# LIC_Rack_BB-00_ext.net
KiCad netlist of a schematic drawn in EAGLE
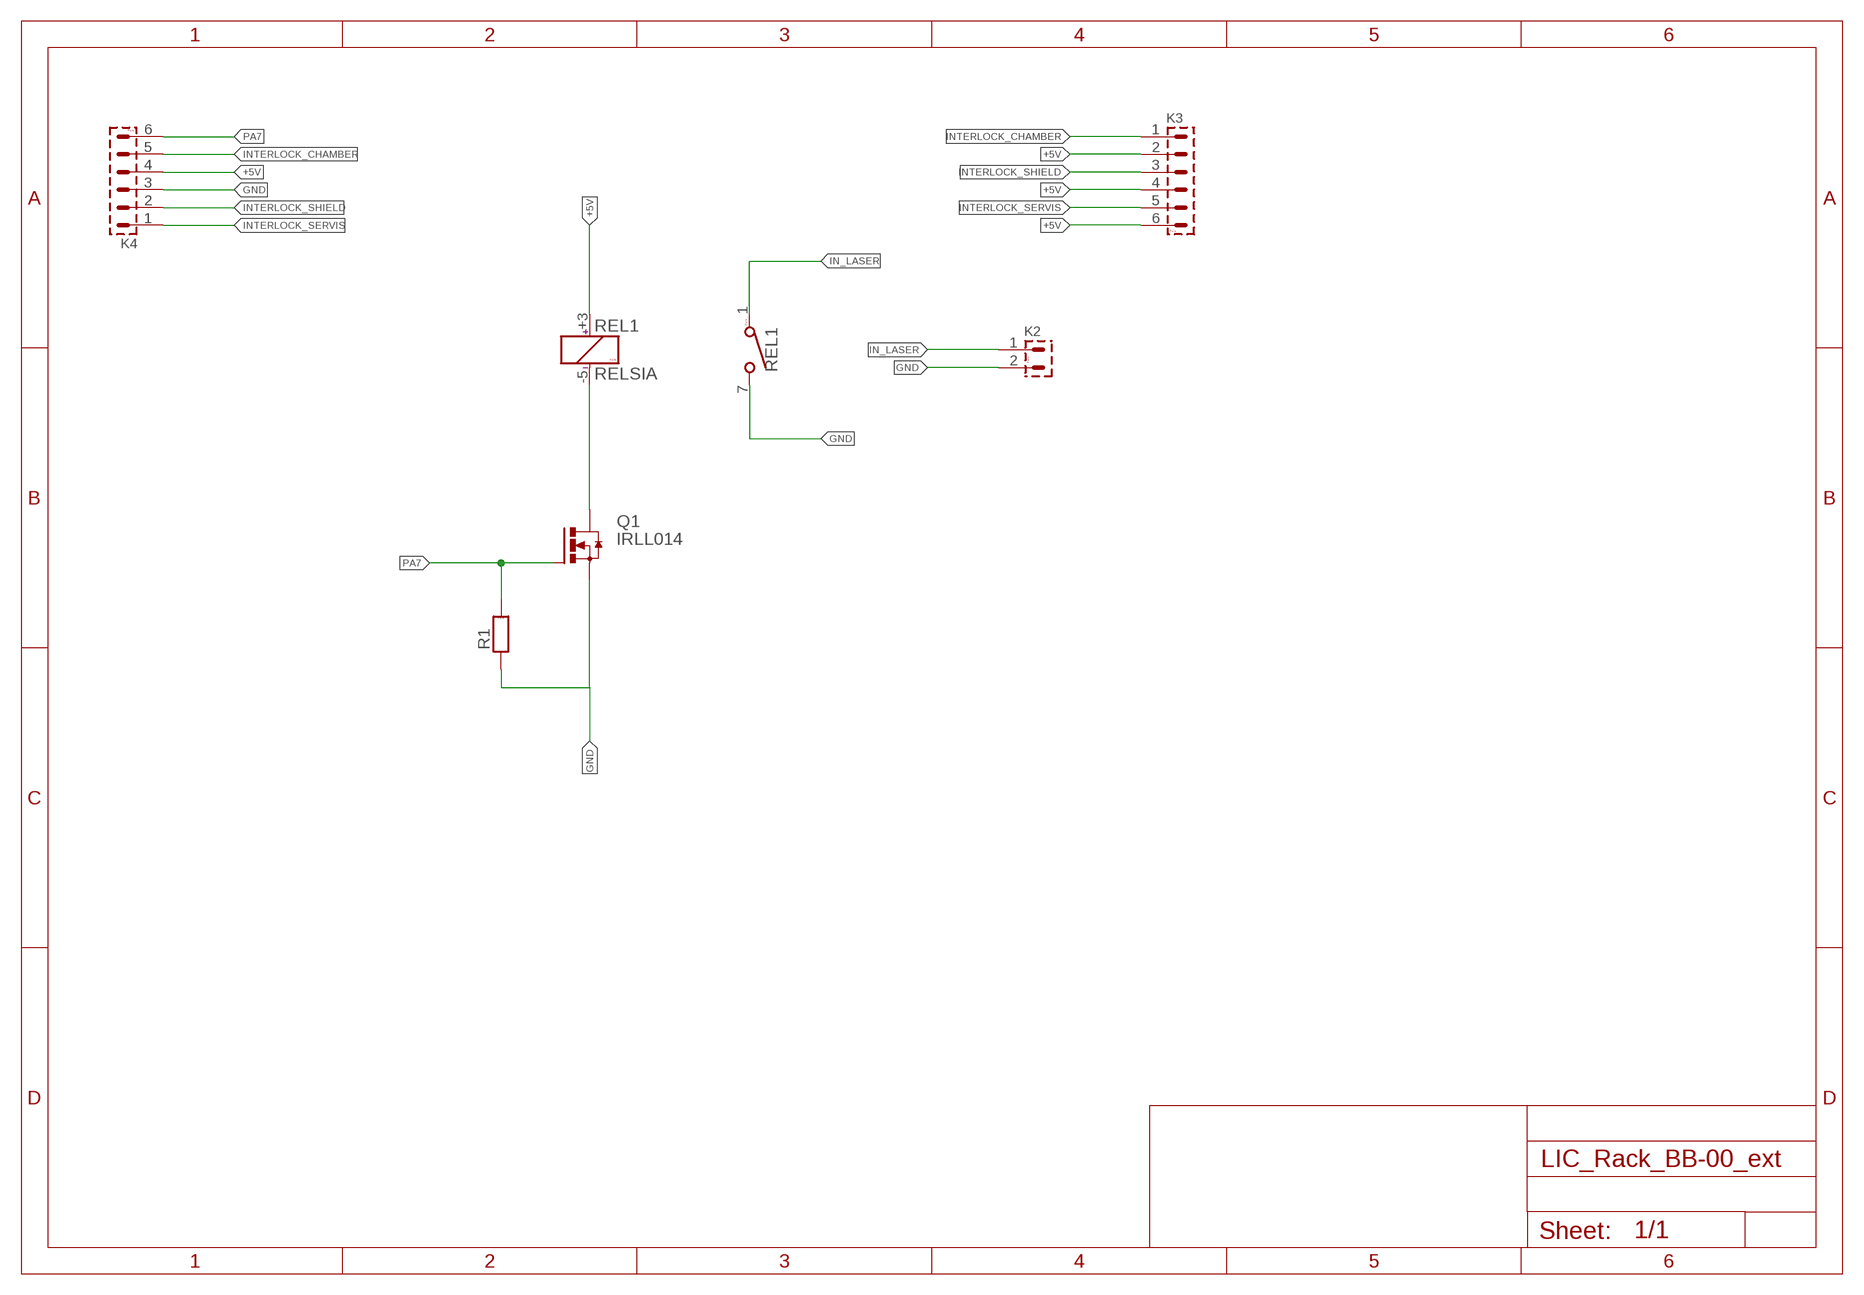
[diagram p0: schematic, sheet 1]

(export (version "E")
  (design (tool "Eeschema 10.0.6"))
  (components
    (comp (ref "K2")
      (value "PSH02-02W")
      (footprint "eagle-import:PSH02-02W")
      (libsource (lib "eagle-import") (part "PSH02-02W"))
    )
    (comp (ref "K3")
      (value "PSH02-06W")
      (footprint "eagle-import:PSH02-06W")
      (libsource (lib "eagle-import") (part "PSH02-06W"))
    )
    (comp (ref "K4")
      (value "PSH02-06W")
      (footprint "eagle-import:PSH02-06W")
      (libsource (lib "eagle-import") (part "PSH02-06W"))
    )
    (comp (ref "Q1")
      (value "IRLL014")
      (footprint "eagle-import:SOT223")
      (libsource (lib "eagle-import") (part "N-HEXFET-2D_?-SOT232"))
    )
    (comp (ref "R1")
      (value "R_1206")
      (footprint "eagle-import:1206")
      (libsource (lib "eagle-import") (part "R_1206"))
    )
    (comp (ref "REL1")
      (value "RELSIA")
      (footprint "eagle-import:RELSIA")
      (libsource (lib "eagle-import") (part "RELSIA??"))
    )
  )
  (nets
    (net (code "1") (name "+5V") (class "Default")
      (node (ref "K3") (pin "2") (pinfunction "2_2") (pintype "passive"))
      (node (ref "K3") (pin "4") (pinfunction "4_4") (pintype "passive"))
      (node (ref "K3") (pin "6") (pinfunction "6_6") (pintype "passive"))
      (node (ref "K4") (pin "4") (pinfunction "4_4") (pintype "passive"))
      (node (ref "REL1") (pin "+3") (pinfunction "C+_+3") (pintype "passive"))
    )
    (net (code "2") (name "GND") (class "Default")
      (node (ref "K2") (pin "2") (pinfunction "2_2") (pintype "passive"))
      (node (ref "K4") (pin "3") (pinfunction "3_3") (pintype "passive"))
      (node (ref "Q1") (pin "3") (pinfunction "S_3") (pintype "passive"))
      (node (ref "R1") (pin "1") (pinfunction "1_1") (pintype "passive"))
      (node (ref "REL1") (pin "7") (pinfunction "2_7") (pintype "passive"))
    )
    (net (code "3") (name "INTERLOCK_CHAMBER") (class "Default")
      (node (ref "K3") (pin "1") (pinfunction "1_1") (pintype "passive"))
      (node (ref "K4") (pin "5") (pinfunction "5_5") (pintype "passive"))
    )
    (net (code "4") (name "INTERLOCK_SERVIS") (class "Default")
      (node (ref "K3") (pin "5") (pinfunction "5_5") (pintype "passive"))
      (node (ref "K4") (pin "1") (pinfunction "1_1") (pintype "passive"))
    )
    (net (code "5") (name "INTERLOCK_SHIELD") (class "Default")
      (node (ref "K3") (pin "3") (pinfunction "3_3") (pintype "passive"))
      (node (ref "K4") (pin "2") (pinfunction "2_2") (pintype "passive"))
    )
    (net (code "6") (name "IN_LASER") (class "Default")
      (node (ref "K2") (pin "1") (pinfunction "1_1") (pintype "passive"))
      (node (ref "REL1") (pin "1") (pinfunction "1_1") (pintype "passive"))
    )
    (net (code "7") (name "Net-(REL1A-C-)") (class "Default")
      (node (ref "Q1") (pin "2") (pinfunction "D_2") (pintype "passive"))
      (node (ref "Q1") (pin "4") (pinfunction "D_4") (pintype "passive"))
      (node (ref "REL1") (pin "-5") (pinfunction "C-_-5") (pintype "passive"))
    )
    (net (code "8") (name "PA7") (class "Default")
      (node (ref "K4") (pin "6") (pinfunction "6_6") (pintype "passive"))
      (node (ref "Q1") (pin "1") (pinfunction "G_1") (pintype "passive"))
      (node (ref "R1") (pin "2") (pinfunction "2_2") (pintype "passive"))
    )
  )
)
